# SAMD11_Breakout.net
KiCad netlist of a schematic drawn in EAGLE
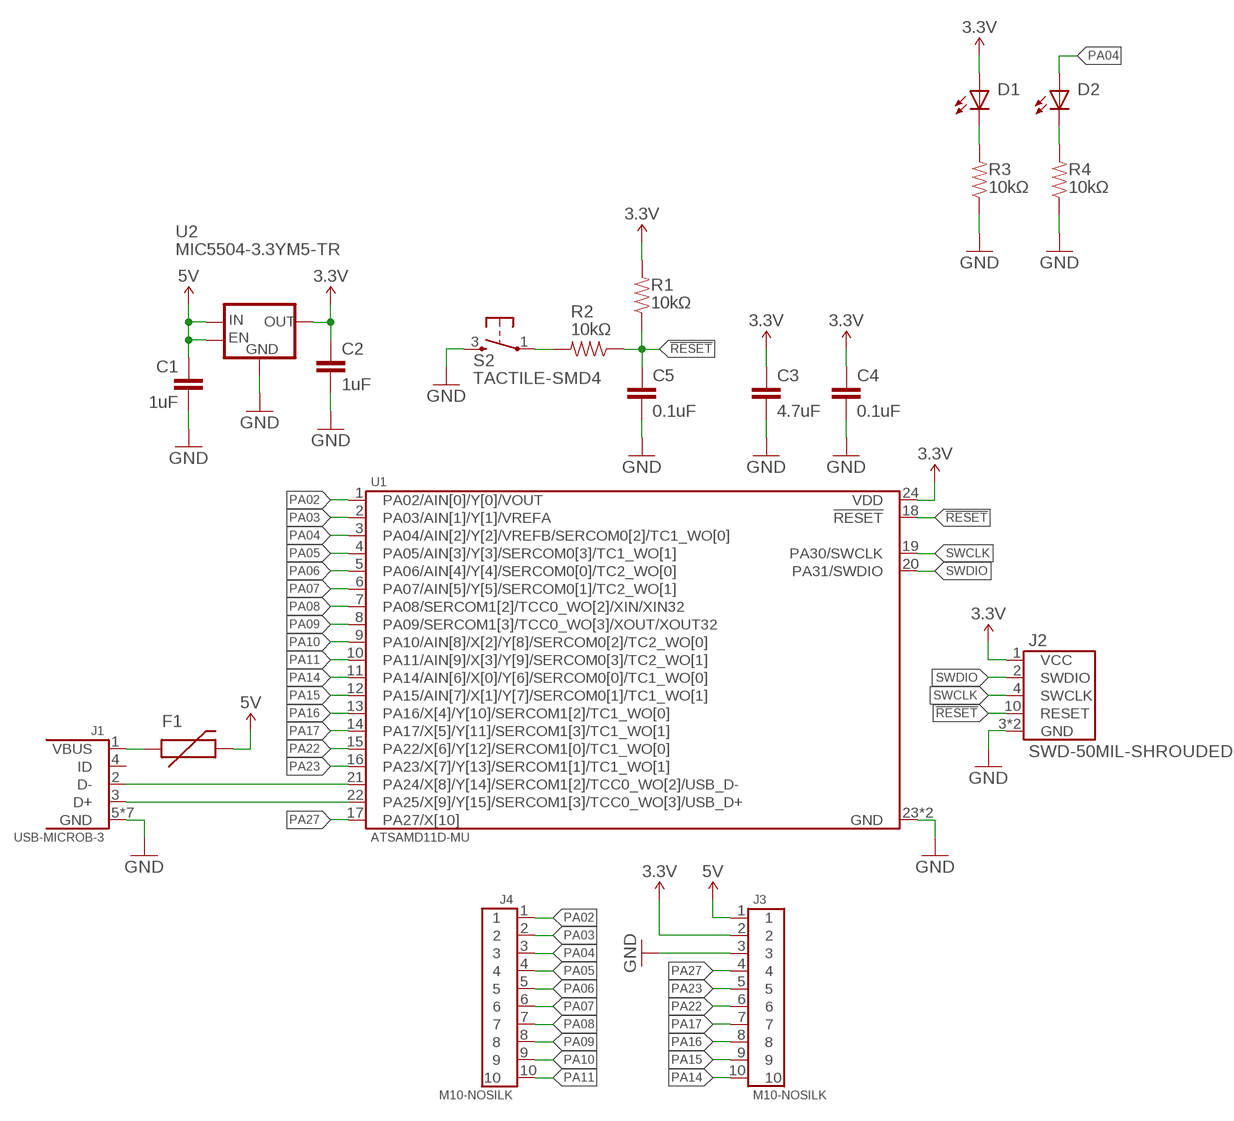
[diagram p0: schematic, sheet 1]

(export (version "E")
  (design (tool "Eeschema 10.0.6"))
  (components
    (comp (ref "C1")
      (value "1uF")
      (footprint "eagle-import:0603-CAP")
      (libsource (lib "eagle-import") (part "CAP-0603"))
    )
    (comp (ref "C2")
      (value "1uF")
      (footprint "eagle-import:0603-CAP")
      (libsource (lib "eagle-import") (part "CAP-0603"))
    )
    (comp (ref "C3")
      (value "4.7uF")
      (footprint "eagle-import:0603-CAP")
      (libsource (lib "eagle-import") (part "CAP-0603"))
    )
    (comp (ref "C4")
      (value "0.1uF")
      (footprint "eagle-import:0603-CAP")
      (libsource (lib "eagle-import") (part "CAP-0603"))
    )
    (comp (ref "C5")
      (value "0.1uF")
      (footprint "eagle-import:0603-CAP")
      (libsource (lib "eagle-import") (part "CAP-0603"))
    )
    (comp (ref "D1")
      (value "LED-0603")
      (footprint "eagle-import:0603-LED")
      (libsource (lib "eagle-import") (part "LED-0603"))
    )
    (comp (ref "D2")
      (value "LED-0603")
      (footprint "eagle-import:0603-LED")
      (libsource (lib "eagle-import") (part "LED-0603"))
    )
    (comp (ref "F1")
      (value "PTC-1206")
      (footprint "eagle-import:1206-PTC")
      (libsource (lib "eagle-import") (part "PTC-1206"))
    )
    (comp (ref "J1")
      (value "USB-MICROB-3")
      (footprint "eagle-import:10118192-0001LF")
      (libsource (lib "eagle-import") (part "USB-MICROB-3"))
    )
    (comp (ref "J2")
      (value "SWD-50MIL-SHROUDED2")
      (footprint "eagle-import:M05X2-50MIL-SHROUD")
      (libsource (lib "eagle-import") (part "SWD-50MIL-SHROUDED2"))
    )
    (comp (ref "J3")
      (value "M10-NOSILK")
      (footprint "eagle-import:M10X1-NOSILK")
      (libsource (lib "eagle-import") (part "M10-NOSILK"))
    )
    (comp (ref "J4")
      (value "M10-NOSILK")
      (footprint "eagle-import:M10X1-NOSILK")
      (libsource (lib "eagle-import") (part "M10-NOSILK"))
    )
    (comp (ref "R1")
      (value "10kΩ")
      (footprint "eagle-import:0603-CAP")
      (libsource (lib "eagle-import") (part "RESISTOR-0603"))
    )
    (comp (ref "R2")
      (value "10kΩ")
      (footprint "eagle-import:0603-CAP")
      (libsource (lib "eagle-import") (part "RESISTOR-0603"))
    )
    (comp (ref "R3")
      (value "10kΩ")
      (footprint "eagle-import:0603-CAP")
      (libsource (lib "eagle-import") (part "RESISTOR-0603"))
    )
    (comp (ref "R4")
      (value "10kΩ")
      (footprint "eagle-import:0603-CAP")
      (libsource (lib "eagle-import") (part "RESISTOR-0603"))
    )
    (comp (ref "S2")
      (value "TACTILE-SMD4")
      (footprint "eagle-import:KMR741NG")
      (libsource (lib "eagle-import") (part "TACTILE-SMD4"))
    )
    (comp (ref "U1")
      (value "ATSAMD11D-MU")
      (footprint "eagle-import:QFN-24")
      (libsource (lib "eagle-import") (part "ATSAMD11D-MU"))
    )
    (comp (ref "U2")
      (value "MIC5504-3.3YM5-TR")
      (footprint "eagle-import:SOT23-5")
      (libsource (lib "eagle-import") (part "MIC5504-3.3YM5-TR"))
    )
  )
  (nets
    (net (code "1") (name "/~{RESET}") (class "Default")
      (node (ref "C5") (pin "1") (pinfunction "1_1") (pintype "passive"))
      (node (ref "J2") (pin "10") (pinfunction "RESET_10") (pintype "bidirectional"))
      (node (ref "R1") (pin "1") (pinfunction "1_1") (pintype "passive"))
      (node (ref "R2") (pin "1") (pinfunction "1_1") (pintype "passive"))
      (node (ref "U1") (pin "18") (pinfunction "~{RESET}_18") (pintype "bidirectional"))
    )
    (net (code "2") (name "3.3V") (class "Default")
      (node (ref "C2") (pin "1") (pinfunction "1_1") (pintype "passive"))
      (node (ref "C3") (pin "1") (pinfunction "1_1") (pintype "passive"))
      (node (ref "C4") (pin "1") (pinfunction "1_1") (pintype "passive"))
      (node (ref "D1") (pin "A") (pinfunction "A_A") (pintype "passive"))
      (node (ref "J2") (pin "1") (pinfunction "VCC_1") (pintype "bidirectional"))
      (node (ref "J3") (pin "2") (pinfunction "2_2") (pintype "bidirectional"))
      (node (ref "R1") (pin "2") (pinfunction "2_2") (pintype "passive"))
      (node (ref "U1") (pin "24") (pinfunction "VDD_24") (pintype "bidirectional"))
      (node (ref "U2") (pin "5") (pinfunction "OUT_5") (pintype "output"))
    )
    (net (code "3") (name "5V") (class "Default")
      (node (ref "C1") (pin "1") (pinfunction "1_1") (pintype "passive"))
      (node (ref "F1") (pin "P$2") (pinfunction "2_P$2") (pintype "bidirectional"))
      (node (ref "J3") (pin "1") (pinfunction "1_1") (pintype "bidirectional"))
      (node (ref "U2") (pin "1") (pinfunction "IN_1") (pintype "input"))
      (node (ref "U2") (pin "3") (pinfunction "EN_3") (pintype "input"))
    )
    (net (code "4") (name "GND") (class "Default")
      (node (ref "C1") (pin "2") (pinfunction "2_2") (pintype "passive"))
      (node (ref "C2") (pin "2") (pinfunction "2_2") (pintype "passive"))
      (node (ref "C3") (pin "2") (pinfunction "2_2") (pintype "passive"))
      (node (ref "C4") (pin "2") (pinfunction "2_2") (pintype "passive"))
      (node (ref "C5") (pin "2") (pinfunction "2_2") (pintype "passive"))
      (node (ref "J1") (pin "5") (pinfunction "GND_5") (pintype "bidirectional"))
      (node (ref "J1") (pin "P$10") (pinfunction "GND_P$10") (pintype "bidirectional"))
      (node (ref "J1") (pin "P$11") (pinfunction "GND_P$11") (pintype "bidirectional"))
      (node (ref "J1") (pin "P$6") (pinfunction "GND_P$6") (pintype "bidirectional"))
      (node (ref "J1") (pin "P$7") (pinfunction "GND_P$7") (pintype "bidirectional"))
      (node (ref "J1") (pin "P$8") (pinfunction "GND_P$8") (pintype "bidirectional"))
      (node (ref "J1") (pin "P$9") (pinfunction "GND_P$9") (pintype "bidirectional"))
      (node (ref "J2") (pin "3") (pinfunction "GND_3") (pintype "bidirectional"))
      (node (ref "J2") (pin "5") (pinfunction "GND_5") (pintype "bidirectional"))
      (node (ref "J3") (pin "3") (pinfunction "3_3") (pintype "bidirectional"))
      (node (ref "R3") (pin "1") (pinfunction "1_1") (pintype "passive"))
      (node (ref "R4") (pin "1") (pinfunction "1_1") (pintype "passive"))
      (node (ref "S2") (pin "3") (pinfunction "3_3") (pintype "passive"))
      (node (ref "U1") (pin "23") (pinfunction "GND_23") (pintype "bidirectional"))
      (node (ref "U1") (pin "P$1") (pinfunction "GND_P$1") (pintype "bidirectional"))
      (node (ref "U2") (pin "2") (pinfunction "GND_2") (pintype "input"))
    )
    (net (code "5") (name "Net-(D1-PadC)") (class "Default")
      (node (ref "D1") (pin "C") (pinfunction "C_C") (pintype "passive"))
      (node (ref "R3") (pin "2") (pinfunction "2_2") (pintype "passive"))
    )
    (net (code "6") (name "Net-(D2-PadC)") (class "Default")
      (node (ref "D2") (pin "C") (pinfunction "C_C") (pintype "passive"))
      (node (ref "R4") (pin "2") (pinfunction "2_2") (pintype "passive"))
    )
    (net (code "7") (name "Net-(F1-1)") (class "Default")
      (node (ref "F1") (pin "P$1") (pinfunction "1_P$1") (pintype "bidirectional"))
      (node (ref "J1") (pin "1") (pinfunction "VBUS_1") (pintype "bidirectional"))
    )
    (net (code "8") (name "Net-(J1-D+)") (class "Default")
      (node (ref "J1") (pin "3") (pinfunction "D+_3") (pintype "bidirectional"))
      (node (ref "U1") (pin "22") (pinfunction "PA25/X[9]/Y[15]/SERCOM1[3]/TCC0_WO[3]/USB_D+_22") (pintype "bidirectional"))
    )
    (net (code "9") (name "Net-(J1-D-)") (class "Default")
      (node (ref "J1") (pin "2") (pinfunction "D-_2") (pintype "bidirectional"))
      (node (ref "U1") (pin "21") (pinfunction "PA24/X[8]/Y[14]/SERCOM1[2]/TCC0_WO[2]/USB_D-_21") (pintype "bidirectional"))
    )
    (net (code "10") (name "Net-(R2-Pad2)") (class "Default")
      (node (ref "R2") (pin "2") (pinfunction "2_2") (pintype "passive"))
      (node (ref "S2") (pin "1") (pinfunction "1_1") (pintype "passive"))
    )
    (net (code "11") (name "PA02") (class "Default")
      (node (ref "J4") (pin "1") (pinfunction "1_1") (pintype "bidirectional"))
      (node (ref "U1") (pin "1") (pinfunction "PA02/AIN[0]/Y[0]/VOUT_1") (pintype "bidirectional"))
    )
    (net (code "12") (name "PA03") (class "Default")
      (node (ref "J4") (pin "2") (pinfunction "2_2") (pintype "bidirectional"))
      (node (ref "U1") (pin "2") (pinfunction "PA03/AIN[1]/Y[1]/VREFA_2") (pintype "bidirectional"))
    )
    (net (code "13") (name "PA04") (class "Default")
      (node (ref "D2") (pin "A") (pinfunction "A_A") (pintype "passive"))
      (node (ref "J4") (pin "3") (pinfunction "3_3") (pintype "bidirectional"))
      (node (ref "U1") (pin "3") (pinfunction "PA04/AIN[2]/Y[2]/VREFB/SERCOM0[2]/TC1_WO[0]_3") (pintype "bidirectional"))
    )
    (net (code "14") (name "PA05") (class "Default")
      (node (ref "J4") (pin "4") (pinfunction "4_4") (pintype "bidirectional"))
      (node (ref "U1") (pin "4") (pinfunction "PA05/AIN[3]/Y[3]/SERCOM0[3]/TC1_WO[1]_4") (pintype "bidirectional"))
    )
    (net (code "15") (name "PA06") (class "Default")
      (node (ref "J4") (pin "5") (pinfunction "5_5") (pintype "bidirectional"))
      (node (ref "U1") (pin "5") (pinfunction "PA06/AIN[4]/Y[4]/SERCOM0[0]/TC2_WO[0]_5") (pintype "bidirectional"))
    )
    (net (code "16") (name "PA07") (class "Default")
      (node (ref "J4") (pin "6") (pinfunction "6_6") (pintype "bidirectional"))
      (node (ref "U1") (pin "6") (pinfunction "PA07/AIN[5]/Y[5]/SERCOM0[1]/TC2_WO[1]_6") (pintype "bidirectional"))
    )
    (net (code "17") (name "PA08") (class "Default")
      (node (ref "J4") (pin "7") (pinfunction "7_7") (pintype "bidirectional"))
      (node (ref "U1") (pin "7") (pinfunction "PA08/SERCOM1[2]/TCC0_WO[2]/XIN/XIN32_7") (pintype "bidirectional"))
    )
    (net (code "18") (name "PA09") (class "Default")
      (node (ref "J4") (pin "8") (pinfunction "8_8") (pintype "bidirectional"))
      (node (ref "U1") (pin "8") (pinfunction "PA09/SERCOM1[3]/TCC0_WO[3]/XOUT/XOUT32_8") (pintype "bidirectional"))
    )
    (net (code "19") (name "PA10") (class "Default")
      (node (ref "J4") (pin "9") (pinfunction "9_9") (pintype "bidirectional"))
      (node (ref "U1") (pin "9") (pinfunction "PA10/AIN[8]/X[2]/Y[8]/SERCOM0[2]/TC2_WO[0]_9") (pintype "bidirectional"))
    )
    (net (code "20") (name "PA11") (class "Default")
      (node (ref "J4") (pin "10") (pinfunction "10_10") (pintype "bidirectional"))
      (node (ref "U1") (pin "10") (pinfunction "PA11/AIN[9]/X[3]/Y[9]/SERCOM0[3]/TC2_WO[1]_10") (pintype "bidirectional"))
    )
    (net (code "21") (name "PA14") (class "Default")
      (node (ref "J3") (pin "10") (pinfunction "10_10") (pintype "bidirectional"))
      (node (ref "U1") (pin "11") (pinfunction "PA14/AIN[6]/X[0]/Y[6]/SERCOM0[0]/TC1_WO[0]_11") (pintype "bidirectional"))
    )
    (net (code "22") (name "PA15") (class "Default")
      (node (ref "J3") (pin "9") (pinfunction "9_9") (pintype "bidirectional"))
      (node (ref "U1") (pin "12") (pinfunction "PA15/AIN[7]/X[1]/Y[7]/SERCOM0[1]/TC1_WO[1]_12") (pintype "bidirectional"))
    )
    (net (code "23") (name "PA16") (class "Default")
      (node (ref "J3") (pin "8") (pinfunction "8_8") (pintype "bidirectional"))
      (node (ref "U1") (pin "13") (pinfunction "PA16/X[4]/Y[10]/SERCOM1[2]/TC1_WO[0]_13") (pintype "bidirectional"))
    )
    (net (code "24") (name "PA17") (class "Default")
      (node (ref "J3") (pin "7") (pinfunction "7_7") (pintype "bidirectional"))
      (node (ref "U1") (pin "14") (pinfunction "PA17/X[5]/Y[11]/SERCOM1[3]/TC1_WO[1]_14") (pintype "bidirectional"))
    )
    (net (code "25") (name "PA22") (class "Default")
      (node (ref "J3") (pin "6") (pinfunction "6_6") (pintype "bidirectional"))
      (node (ref "U1") (pin "15") (pinfunction "PA22/X[6]/Y[12]/SERCOM1[0]/TC1_WO[0]_15") (pintype "bidirectional"))
    )
    (net (code "26") (name "PA23") (class "Default")
      (node (ref "J3") (pin "5") (pinfunction "5_5") (pintype "bidirectional"))
      (node (ref "U1") (pin "16") (pinfunction "PA23/X[7]/Y[13]/SERCOM1[1]/TC1_WO[1]_16") (pintype "bidirectional"))
    )
    (net (code "27") (name "PA27") (class "Default")
      (node (ref "J3") (pin "4") (pinfunction "4_4") (pintype "bidirectional"))
      (node (ref "U1") (pin "17") (pinfunction "PA27/X[10]_17") (pintype "bidirectional"))
    )
    (net (code "28") (name "SWCLK") (class "Default")
      (node (ref "J2") (pin "4") (pinfunction "SWCLK_4") (pintype "bidirectional"))
      (node (ref "U1") (pin "19") (pinfunction "PA30/SWCLK_19") (pintype "bidirectional"))
    )
    (net (code "29") (name "SWDIO") (class "Default")
      (node (ref "J2") (pin "2") (pinfunction "SWDIO_2") (pintype "bidirectional"))
      (node (ref "U1") (pin "20") (pinfunction "PA31/SWDIO_20") (pintype "bidirectional"))
    )
    (net (code "30") (name "unconnected-(J1-ID-Pad4)") (class "Default")
      (node (ref "J1") (pin "4") (pinfunction "ID_4") (pintype "bidirectional"))
    )
  )
)
